# MEMMORY.net
KiCad netlist of a schematic drawn in Altium Designer
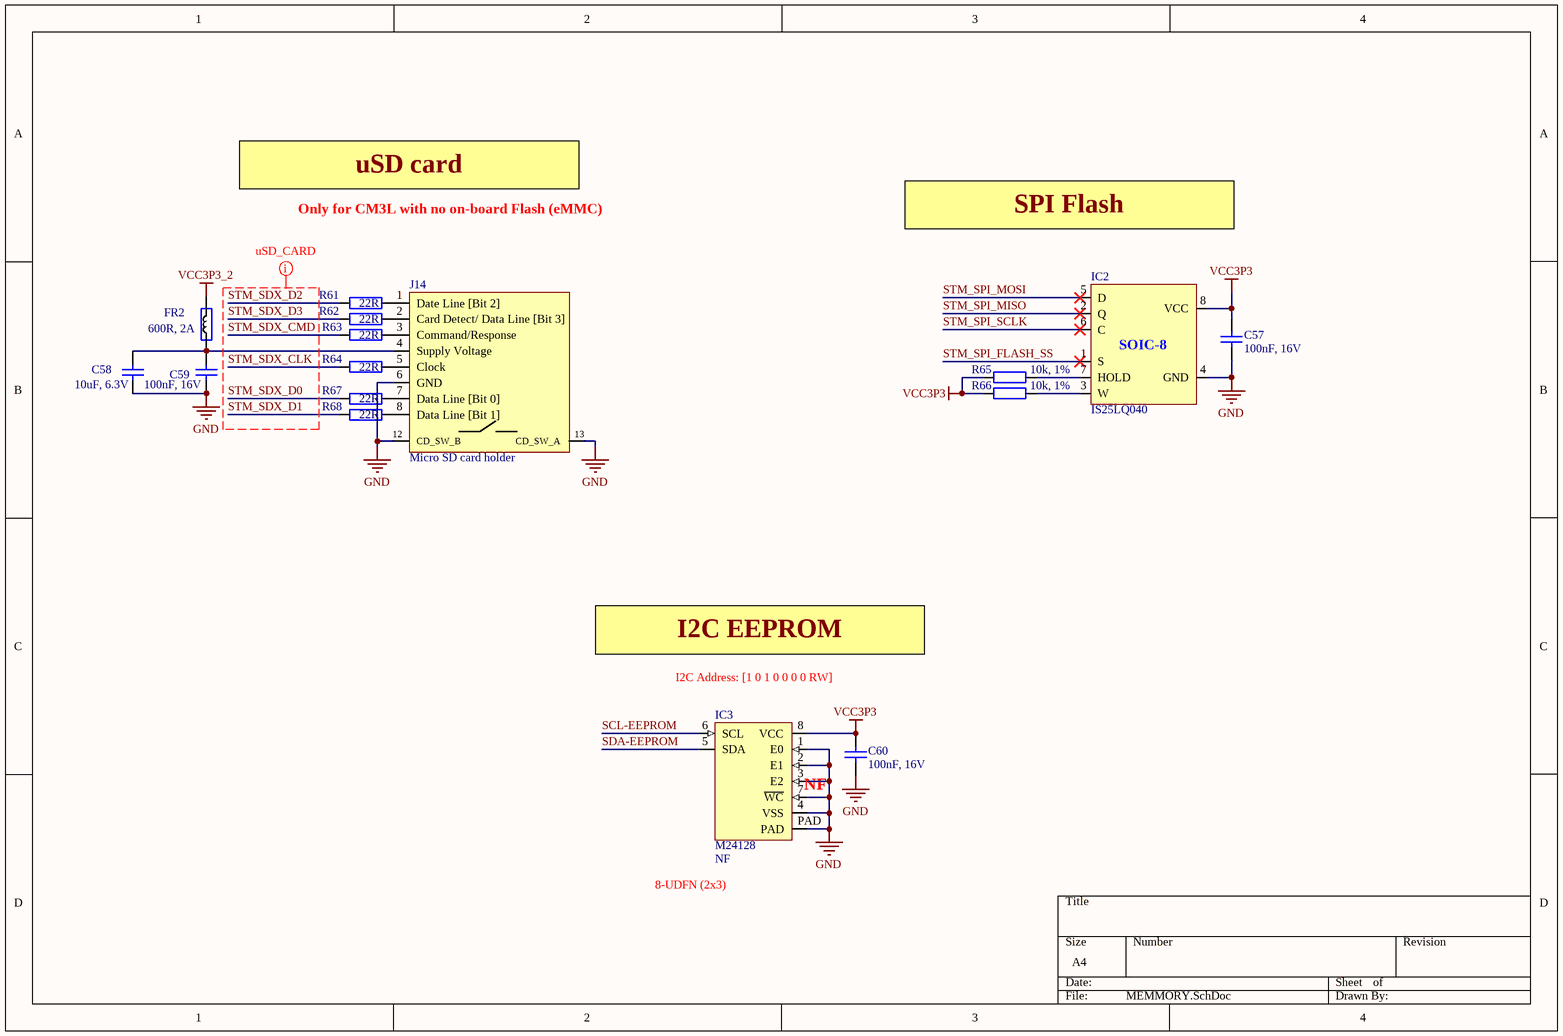
[diagram p0: MEMMORY.SchDoc]

(export (version "E")
  (design (tool "Eeschema 10.0.6"))
  (components
    (comp (ref "C57")
      (value "100nF, 16V")
      (footprint "CAP0402")
      (fields
        (field (name "TOLERANCE") "10 %")
        (field (name "MANUFACTURER") "Murata Electronics")
        (field (name "MANUFACTURER PART NUMBER") "GRM155R71C104KA88D")
      )
      (libsource (lib "LimeFPGAboard_schLib") (part "Cap_0603"))
    )
    (comp (ref "C58")
      (value "10uF, 6.3V")
      (footprint "CAP0603")
      (fields (field (name "TOLERANCE") "±20%") (field (name "MANUFACTURER") "Yageo"))
      (libsource (lib "LimeFPGAboard_schLib") (part "Cap_0603"))
    )
    (comp (ref "C59")
      (value "100nF, 16V")
      (footprint "CAP0402")
      (fields (field (name "TOLERANCE") "10 %") (field (name "MANUFACTURER") "Murata Electronics"))
      (libsource (lib "LimeFPGAboard_schLib") (part "Cap_0603"))
    )
    (comp (ref "C60")
      (value "100nF, 16V")
      (footprint "CAP0402")
      (fields
        (field (name "TOLERANCE") "10 %")
        (field (name "MANUFACTURER") "Murata Electronics")
        (field (name "MANUFACTURER PART NUMBER") "GRM155R71C104KA88D")
      )
      (libsource (lib "LimeFPGAboard_schLib") (part "Cap_0603"))
    )
    (comp (ref "FR2")
      (value "600R, 2A")
      (footprint "RES0805")
      (fields (field (name "MANUFACTURER") "TDK Corporation"))
      (libsource (lib "LimeMicroAltiumLib_schLib") (part "Ferrite"))
    )
    (comp (ref "IC2")
      (value "IS25LQ040")
      (footprint "M25P40-VMN6TPB_SO8N")
      (fields (field (name "MANUFACTURER") "ISSI, Integrated Silicon Solution Inc"))
      (libsource (lib "LimeFPGAboard_schLib") (part "M25P40"))
    )
    (comp (ref "IC3")
      (value "M24128")
      (footprint "M24128-DFMC6TG")
      (fields (field (name "MANUFACTURER") "STMicroelectronics") (field (name "ASSEMBLY INFO") "NF"))
      (libsource (lib "LimeMicroAltiumLib_schLib") (part "M24128-DFMC6TG"))
    )
    (comp (ref "J14")
      (value "Micro SD card holder")
      (footprint "MICRO_SD_CARD_114-00841-68_v2")
      (fields (field (name "MANUFACTURER") "Amphenol Commercial Products"))
      (libsource (lib "LimeMicroAltiumLib_schLib_r01") (part "MICRO_SD_114-00841-68"))
    )
    (comp (ref "R61")
      (value "22R")
      (footprint "RES0402")
      (fields (field (name "TOLERANCE") "±1%") (field (name "MANUFACTURER") "Yageo"))
      (libsource (lib "LimeFPGAboard_schLib") (part "Res_0402"))
    )
    (comp (ref "R62")
      (value "22R")
      (footprint "RES0402")
      (fields (field (name "TOLERANCE") "±1%") (field (name "MANUFACTURER") "Yageo"))
      (libsource (lib "LimeFPGAboard_schLib") (part "Res_0402"))
    )
    (comp (ref "R63")
      (value "22R")
      (footprint "RES0402")
      (fields (field (name "TOLERANCE") "±1%") (field (name "MANUFACTURER") "Yageo"))
      (libsource (lib "LimeFPGAboard_schLib") (part "Res_0402"))
    )
    (comp (ref "R64")
      (value "22R")
      (footprint "RES0402")
      (fields (field (name "TOLERANCE") "±1%") (field (name "MANUFACTURER") "Yageo"))
      (libsource (lib "LimeFPGAboard_schLib") (part "Res_0402"))
    )
    (comp (ref "R65")
      (value "10k, 1%")
      (footprint "RES0402")
      (fields (field (name "MANUFACTURER") "Yageo") (field (name "TOLERANCE") "±1%"))
      (libsource (lib "LimeMicroAltiumLib_schLib") (part "Res_0402"))
    )
    (comp (ref "R66")
      (value "10k, 1%")
      (footprint "RES0402")
      (fields (field (name "MANUFACTURER") "Yageo") (field (name "TOLERANCE") "±1%"))
      (libsource (lib "LimeMicroAltiumLib_schLib") (part "Res_0402"))
    )
    (comp (ref "R67")
      (value "22R")
      (footprint "RES0402")
      (fields (field (name "TOLERANCE") "±1%") (field (name "MANUFACTURER") "Yageo"))
      (libsource (lib "LimeFPGAboard_schLib") (part "Res_0402"))
    )
    (comp (ref "R68")
      (value "22R")
      (footprint "RES0402")
      (fields (field (name "TOLERANCE") "±1%") (field (name "MANUFACTURER") "Yageo"))
      (libsource (lib "LimeFPGAboard_schLib") (part "Res_0402"))
    )
  )
  (nets
    (net (code "1") (name "/SCL-EEPROM") (class "Default")
      (node (ref "IC3") (pin "6") (pinfunction "SCL_6") (pintype "input"))
    )
    (net (code "2") (name "/SDA-EEPROM") (class "Default")
      (node (ref "IC3") (pin "5") (pinfunction "SDA_5") (pintype "bidirectional"))
    )
    (net (code "3") (name "/STM_SDX_CLK") (class "Default")
      (node (ref "R64") (pin "1") (pinfunction "1_1") (pintype "passive"))
    )
    (net (code "4") (name "/STM_SDX_CMD") (class "Default")
      (node (ref "R63") (pin "1") (pinfunction "1_1") (pintype "passive"))
    )
    (net (code "5") (name "/STM_SDX_D0") (class "Default")
      (node (ref "R67") (pin "1") (pinfunction "1_1") (pintype "passive"))
    )
    (net (code "6") (name "/STM_SDX_D1") (class "Default")
      (node (ref "R68") (pin "1") (pinfunction "1_1") (pintype "passive"))
    )
    (net (code "7") (name "/STM_SDX_D2") (class "Default")
      (node (ref "R61") (pin "1") (pinfunction "1_1") (pintype "passive"))
    )
    (net (code "8") (name "/STM_SDX_D3") (class "Default")
      (node (ref "R62") (pin "1") (pinfunction "1_1") (pintype "passive"))
    )
    (net (code "9") (name "/STM_SPI_FLASH_SS") (class "Default")
      (node (ref "IC2") (pin "1") (pinfunction "S_1") (pintype "passive+no_connect"))
    )
    (net (code "10") (name "/STM_SPI_MISO") (class "Default")
      (node (ref "IC2") (pin "2") (pinfunction "Q_2") (pintype "passive+no_connect"))
    )
    (net (code "11") (name "/STM_SPI_MOSI") (class "Default")
      (node (ref "IC2") (pin "5") (pinfunction "D_5") (pintype "passive+no_connect"))
    )
    (net (code "12") (name "/STM_SPI_SCLK") (class "Default")
      (node (ref "IC2") (pin "6") (pinfunction "C_6") (pintype "passive+no_connect"))
    )
    (net (code "13") (name "GND") (class "Default")
      (node (ref "C57") (pin "2") (pinfunction "2_2") (pintype "passive"))
      (node (ref "C58") (pin "1") (pinfunction "1_1") (pintype "passive"))
      (node (ref "C59") (pin "2") (pinfunction "2_2") (pintype "passive"))
      (node (ref "C60") (pin "2") (pinfunction "2_2") (pintype "passive"))
      (node (ref "IC2") (pin "4") (pinfunction "GND_4") (pintype "passive"))
      (node (ref "IC3") (pin "1") (pinfunction "E0_1") (pintype "input"))
      (node (ref "IC3") (pin "2") (pinfunction "E1_2") (pintype "input"))
      (node (ref "IC3") (pin "3") (pinfunction "E2_3") (pintype "input"))
      (node (ref "IC3") (pin "4") (pinfunction "VSS_4") (pintype "power_in"))
      (node (ref "IC3") (pin "7") (pinfunction "~{WC}_7") (pintype "input"))
      (node (ref "IC3") (pin "PAD") (pinfunction "PAD_PAD") (pintype "power_in"))
      (node (ref "J14") (pin "12") (pinfunction "CD_SW_B_12") (pintype "passive"))
      (node (ref "J14") (pin "13") (pinfunction "CD_SW_A_13") (pintype "passive"))
      (node (ref "J14") (pin "6") (pinfunction "GND_6") (pintype "passive"))
    )
    (net (code "14") (name "Net-(IC2-HOLD)") (class "Default")
      (node (ref "IC2") (pin "7") (pinfunction "HOLD_7") (pintype "passive"))
      (node (ref "R65") (pin "2") (pinfunction "2_2") (pintype "passive"))
    )
    (net (code "15") (name "Net-(IC2-W)") (class "Default")
      (node (ref "IC2") (pin "3") (pinfunction "W_3") (pintype "passive"))
      (node (ref "R66") (pin "2") (pinfunction "2_2") (pintype "passive"))
    )
    (net (code "16") (name "Net-(J14-Card_Detect{slash}_Data_Line_[Bit_3])") (class "Default")
      (node (ref "J14") (pin "2") (pinfunction "Card_Detect/_Data_Line_[Bit_3]_2") (pintype "passive"))
      (node (ref "R62") (pin "2") (pinfunction "2_2") (pintype "passive"))
    )
    (net (code "17") (name "Net-(J14-Clock)") (class "Default")
      (node (ref "J14") (pin "5") (pinfunction "Clock_5") (pintype "passive"))
      (node (ref "R64") (pin "2") (pinfunction "2_2") (pintype "passive"))
    )
    (net (code "18") (name "Net-(J14-Command{slash}Response)") (class "Default")
      (node (ref "J14") (pin "3") (pinfunction "Command/Response_3") (pintype "passive"))
      (node (ref "R63") (pin "2") (pinfunction "2_2") (pintype "passive"))
    )
    (net (code "19") (name "Net-(J14-Data_Line_[Bit_0])") (class "Default")
      (node (ref "J14") (pin "7") (pinfunction "Data_Line_[Bit_0]_7") (pintype "passive"))
      (node (ref "R67") (pin "2") (pinfunction "2_2") (pintype "passive"))
    )
    (net (code "20") (name "Net-(J14-Data_Line_[Bit_1])") (class "Default")
      (node (ref "J14") (pin "8") (pinfunction "Data_Line_[Bit_1]_8") (pintype "passive"))
      (node (ref "R68") (pin "2") (pinfunction "2_2") (pintype "passive"))
    )
    (net (code "21") (name "Net-(J14-Date_Line_[Bit_2])") (class "Default")
      (node (ref "J14") (pin "1") (pinfunction "Date_Line_[Bit_2]_1") (pintype "passive"))
      (node (ref "R61") (pin "2") (pinfunction "2_2") (pintype "passive"))
    )
    (net (code "22") (name "Net-(J14-Supply_Voltage)") (class "Default")
      (node (ref "C58") (pin "2") (pinfunction "2_2") (pintype "passive"))
      (node (ref "C59") (pin "1") (pinfunction "1_1") (pintype "passive"))
      (node (ref "FR2") (pin "1") (pinfunction "1_1") (pintype "passive"))
      (node (ref "J14") (pin "4") (pinfunction "Supply_Voltage_4") (pintype "passive"))
    )
    (net (code "23") (name "VCC3P3") (class "Default")
      (node (ref "C57") (pin "1") (pinfunction "1_1") (pintype "passive"))
      (node (ref "C60") (pin "1") (pinfunction "1_1") (pintype "passive"))
      (node (ref "IC2") (pin "8") (pinfunction "VCC_8") (pintype "passive"))
      (node (ref "IC3") (pin "8") (pinfunction "VCC_8") (pintype "power_in"))
      (node (ref "R65") (pin "1") (pinfunction "1_1") (pintype "passive"))
      (node (ref "R66") (pin "1") (pinfunction "1_1") (pintype "passive"))
    )
    (net (code "24") (name "VCC3P3_2") (class "Default")
      (node (ref "FR2") (pin "2") (pinfunction "2_2") (pintype "passive"))
    )
  )
)
